# SCH_PCB-Final_2025-01-21.net
KiCad netlist of a schematic drawn in EasyEDA
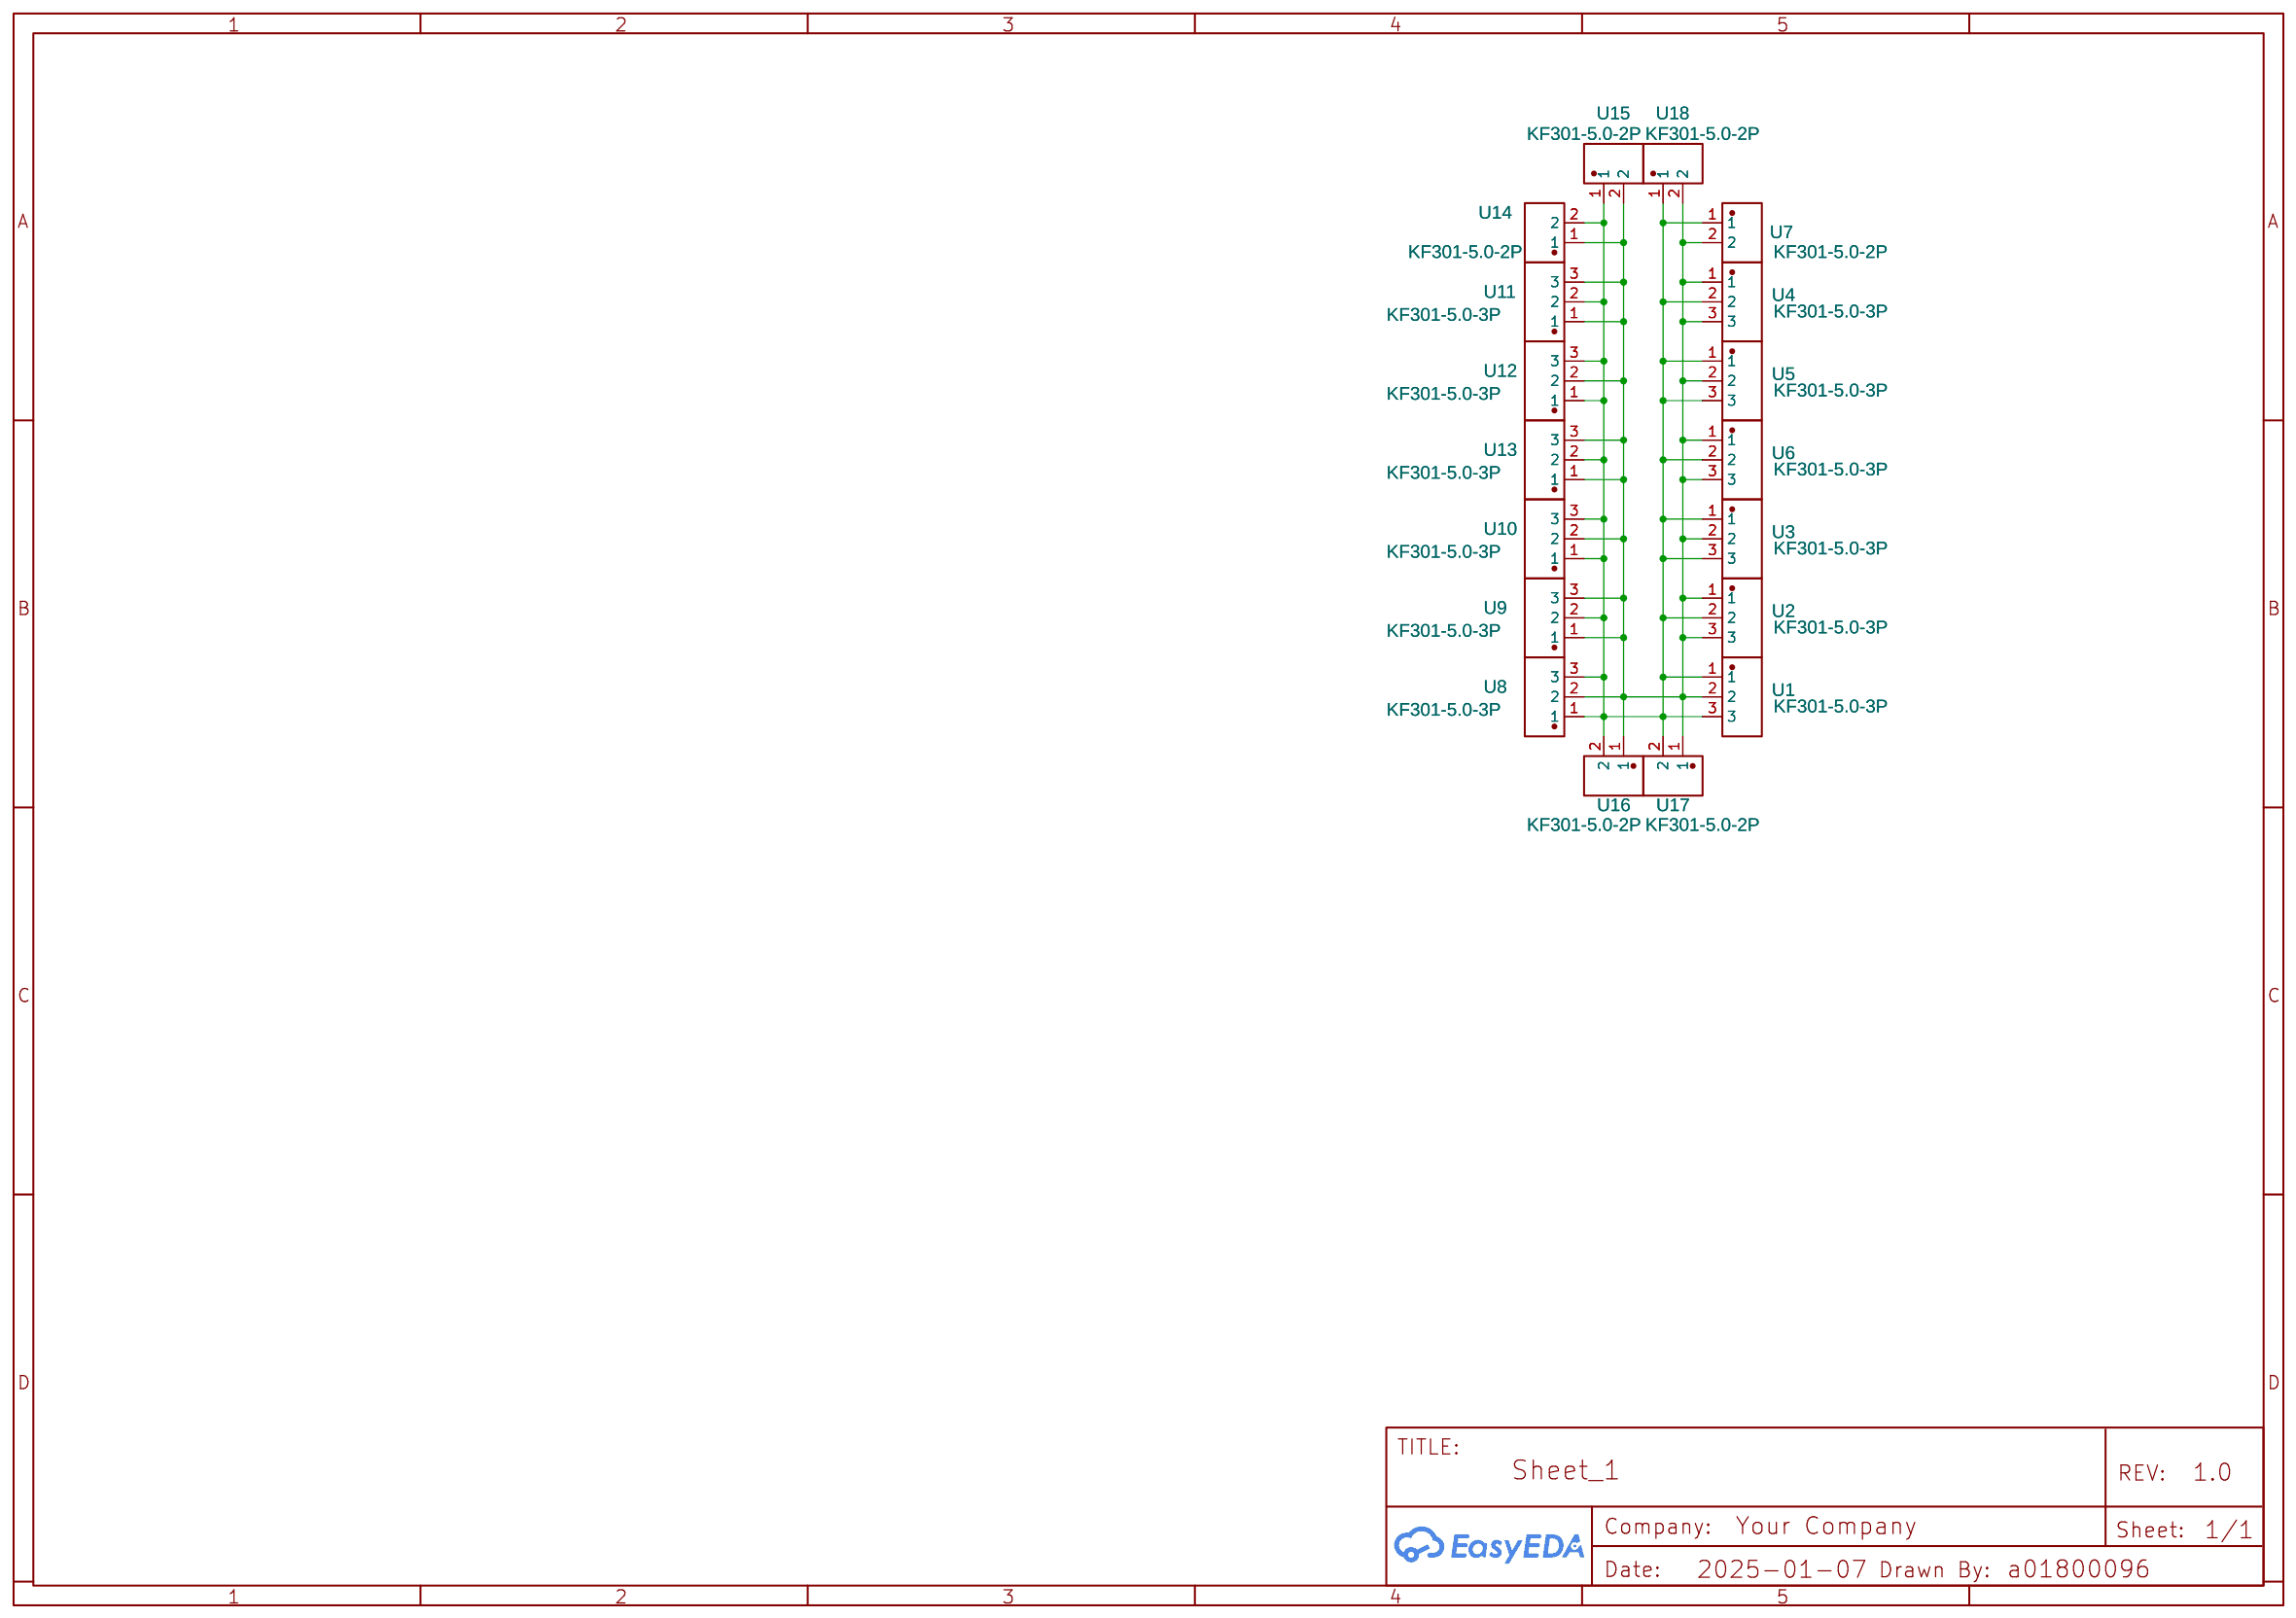
[diagram p0: schematic sheet]

(export (version "E")
  (design (tool "Eeschema 10.0.6"))
  (components
    (comp (ref "U1")
      (value "KF301-5.0-3P")
      (fields (field (name "Manufacturer") "KEFA(科发)"))
      (libsource (lib "") (part "KF301-5.0-3P"))
    )
    (comp (ref "U2")
      (value "KF301-5.0-3P")
      (fields (field (name "Manufacturer") "KEFA(科发)"))
      (libsource (lib "") (part "KF301-5.0-3P"))
    )
    (comp (ref "U3")
      (value "KF301-5.0-3P")
      (fields (field (name "Manufacturer") "KEFA(科发)"))
      (libsource (lib "") (part "KF301-5.0-3P"))
    )
    (comp (ref "U4")
      (value "KF301-5.0-3P")
      (fields (field (name "Manufacturer") "KEFA(科发)"))
      (libsource (lib "") (part "KF301-5.0-3P"))
    )
    (comp (ref "U5")
      (value "KF301-5.0-3P")
      (fields (field (name "Manufacturer") "KEFA(科发)"))
      (libsource (lib "") (part "KF301-5.0-3P"))
    )
    (comp (ref "U6")
      (value "KF301-5.0-3P")
      (fields (field (name "Manufacturer") "KEFA(科发)"))
      (libsource (lib "") (part "KF301-5.0-3P"))
    )
    (comp (ref "U7")
      (value "KF301-5.0-2P")
      (fields (field (name "Manufacturer") "KEFA(科发)"))
      (libsource (lib "") (part "KF301-5.0-2P"))
    )
    (comp (ref "U8")
      (value "KF301-5.0-3P")
      (fields (field (name "Manufacturer") "KEFA(科发)"))
      (libsource (lib "") (part "KF301-5.0-3P_1"))
    )
    (comp (ref "U9")
      (value "KF301-5.0-3P")
      (fields (field (name "Manufacturer") "KEFA(科发)"))
      (libsource (lib "") (part "KF301-5.0-3P_1"))
    )
    (comp (ref "U10")
      (value "KF301-5.0-3P")
      (fields (field (name "Manufacturer") "KEFA(科发)"))
      (libsource (lib "") (part "KF301-5.0-3P_1"))
    )
    (comp (ref "U11")
      (value "KF301-5.0-3P")
      (fields (field (name "Manufacturer") "KEFA(科发)"))
      (libsource (lib "") (part "KF301-5.0-3P_1"))
    )
    (comp (ref "U12")
      (value "KF301-5.0-3P")
      (fields (field (name "Manufacturer") "KEFA(科发)"))
      (libsource (lib "") (part "KF301-5.0-3P_1"))
    )
    (comp (ref "U13")
      (value "KF301-5.0-3P")
      (fields (field (name "Manufacturer") "KEFA(科发)"))
      (libsource (lib "") (part "KF301-5.0-3P_1"))
    )
    (comp (ref "U14")
      (value "KF301-5.0-2P")
      (fields (field (name "Manufacturer") "KEFA(科发)"))
      (libsource (lib "") (part "KF301-5.0-2P_2"))
    )
    (comp (ref "U15")
      (value "KF301-5.0-2P")
      (fields (field (name "Manufacturer") "KEFA(科发)"))
      (libsource (lib "") (part "KF301-5.0-2P_1"))
    )
    (comp (ref "U16")
      (value "KF301-5.0-2P")
      (fields (field (name "Manufacturer") "KEFA(科发)"))
      (libsource (lib "") (part "KF301-5.0-2P_3"))
    )
    (comp (ref "U17")
      (value "KF301-5.0-2P")
      (fields (field (name "Manufacturer") "KEFA(科发)"))
      (libsource (lib "") (part "KF301-5.0-2P_3"))
    )
    (comp (ref "U18")
      (value "KF301-5.0-2P")
      (fields (field (name "Manufacturer") "KEFA(科发)"))
      (libsource (lib "") (part "KF301-5.0-2P_1"))
    )
  )
  (nets
    (net (code "1") (name "Net-(U1-Pad1)") (class "Default")
      (node (ref "U1") (pin "1") (pinfunction "1_1") (pintype "unspecified"))
      (node (ref "U1") (pin "3") (pinfunction "3_3") (pintype "unspecified"))
      (node (ref "U10") (pin "1") (pinfunction "1_1") (pintype "unspecified"))
      (node (ref "U10") (pin "3") (pinfunction "3_3") (pintype "unspecified"))
      (node (ref "U11") (pin "2") (pinfunction "2_2") (pintype "unspecified"))
      (node (ref "U12") (pin "1") (pinfunction "1_1") (pintype "unspecified"))
      (node (ref "U12") (pin "3") (pinfunction "3_3") (pintype "unspecified"))
      (node (ref "U13") (pin "2") (pinfunction "2_2") (pintype "unspecified"))
      (node (ref "U14") (pin "2") (pinfunction "2_2") (pintype "unspecified"))
      (node (ref "U15") (pin "1") (pinfunction "1_1") (pintype "unspecified"))
      (node (ref "U16") (pin "2") (pinfunction "2_2") (pintype "unspecified"))
      (node (ref "U17") (pin "2") (pinfunction "2_2") (pintype "unspecified"))
      (node (ref "U18") (pin "1") (pinfunction "1_1") (pintype "unspecified"))
      (node (ref "U2") (pin "2") (pinfunction "2_2") (pintype "unspecified"))
      (node (ref "U3") (pin "1") (pinfunction "1_1") (pintype "unspecified"))
      (node (ref "U3") (pin "3") (pinfunction "3_3") (pintype "unspecified"))
      (node (ref "U4") (pin "2") (pinfunction "2_2") (pintype "unspecified"))
      (node (ref "U5") (pin "1") (pinfunction "1_1") (pintype "unspecified"))
      (node (ref "U5") (pin "3") (pinfunction "3_3") (pintype "unspecified"))
      (node (ref "U6") (pin "2") (pinfunction "2_2") (pintype "unspecified"))
      (node (ref "U7") (pin "1") (pinfunction "1_1") (pintype "unspecified"))
      (node (ref "U8") (pin "1") (pinfunction "1_1") (pintype "unspecified"))
      (node (ref "U8") (pin "3") (pinfunction "3_3") (pintype "unspecified"))
      (node (ref "U9") (pin "2") (pinfunction "2_2") (pintype "unspecified"))
    )
    (net (code "2") (name "Net-(U1-Pad2)") (class "Default")
      (node (ref "U1") (pin "2") (pinfunction "2_2") (pintype "unspecified"))
      (node (ref "U10") (pin "2") (pinfunction "2_2") (pintype "unspecified"))
      (node (ref "U11") (pin "1") (pinfunction "1_1") (pintype "unspecified"))
      (node (ref "U11") (pin "3") (pinfunction "3_3") (pintype "unspecified"))
      (node (ref "U12") (pin "2") (pinfunction "2_2") (pintype "unspecified"))
      (node (ref "U13") (pin "1") (pinfunction "1_1") (pintype "unspecified"))
      (node (ref "U13") (pin "3") (pinfunction "3_3") (pintype "unspecified"))
      (node (ref "U14") (pin "1") (pinfunction "1_1") (pintype "unspecified"))
      (node (ref "U15") (pin "2") (pinfunction "2_2") (pintype "unspecified"))
      (node (ref "U16") (pin "1") (pinfunction "1_1") (pintype "unspecified"))
      (node (ref "U17") (pin "1") (pinfunction "1_1") (pintype "unspecified"))
      (node (ref "U18") (pin "2") (pinfunction "2_2") (pintype "unspecified"))
      (node (ref "U2") (pin "1") (pinfunction "1_1") (pintype "unspecified"))
      (node (ref "U2") (pin "3") (pinfunction "3_3") (pintype "unspecified"))
      (node (ref "U3") (pin "2") (pinfunction "2_2") (pintype "unspecified"))
      (node (ref "U4") (pin "1") (pinfunction "1_1") (pintype "unspecified"))
      (node (ref "U4") (pin "3") (pinfunction "3_3") (pintype "unspecified"))
      (node (ref "U5") (pin "2") (pinfunction "2_2") (pintype "unspecified"))
      (node (ref "U6") (pin "1") (pinfunction "1_1") (pintype "unspecified"))
      (node (ref "U6") (pin "3") (pinfunction "3_3") (pintype "unspecified"))
      (node (ref "U7") (pin "2") (pinfunction "2_2") (pintype "unspecified"))
      (node (ref "U8") (pin "2") (pinfunction "2_2") (pintype "unspecified"))
      (node (ref "U9") (pin "1") (pinfunction "1_1") (pintype "unspecified"))
      (node (ref "U9") (pin "3") (pinfunction "3_3") (pintype "unspecified"))
    )
  )
)
